# ProDocument_Board1612_2023-10-08.net
KiCad netlist of a schematic drawn in EasyEDA Pro
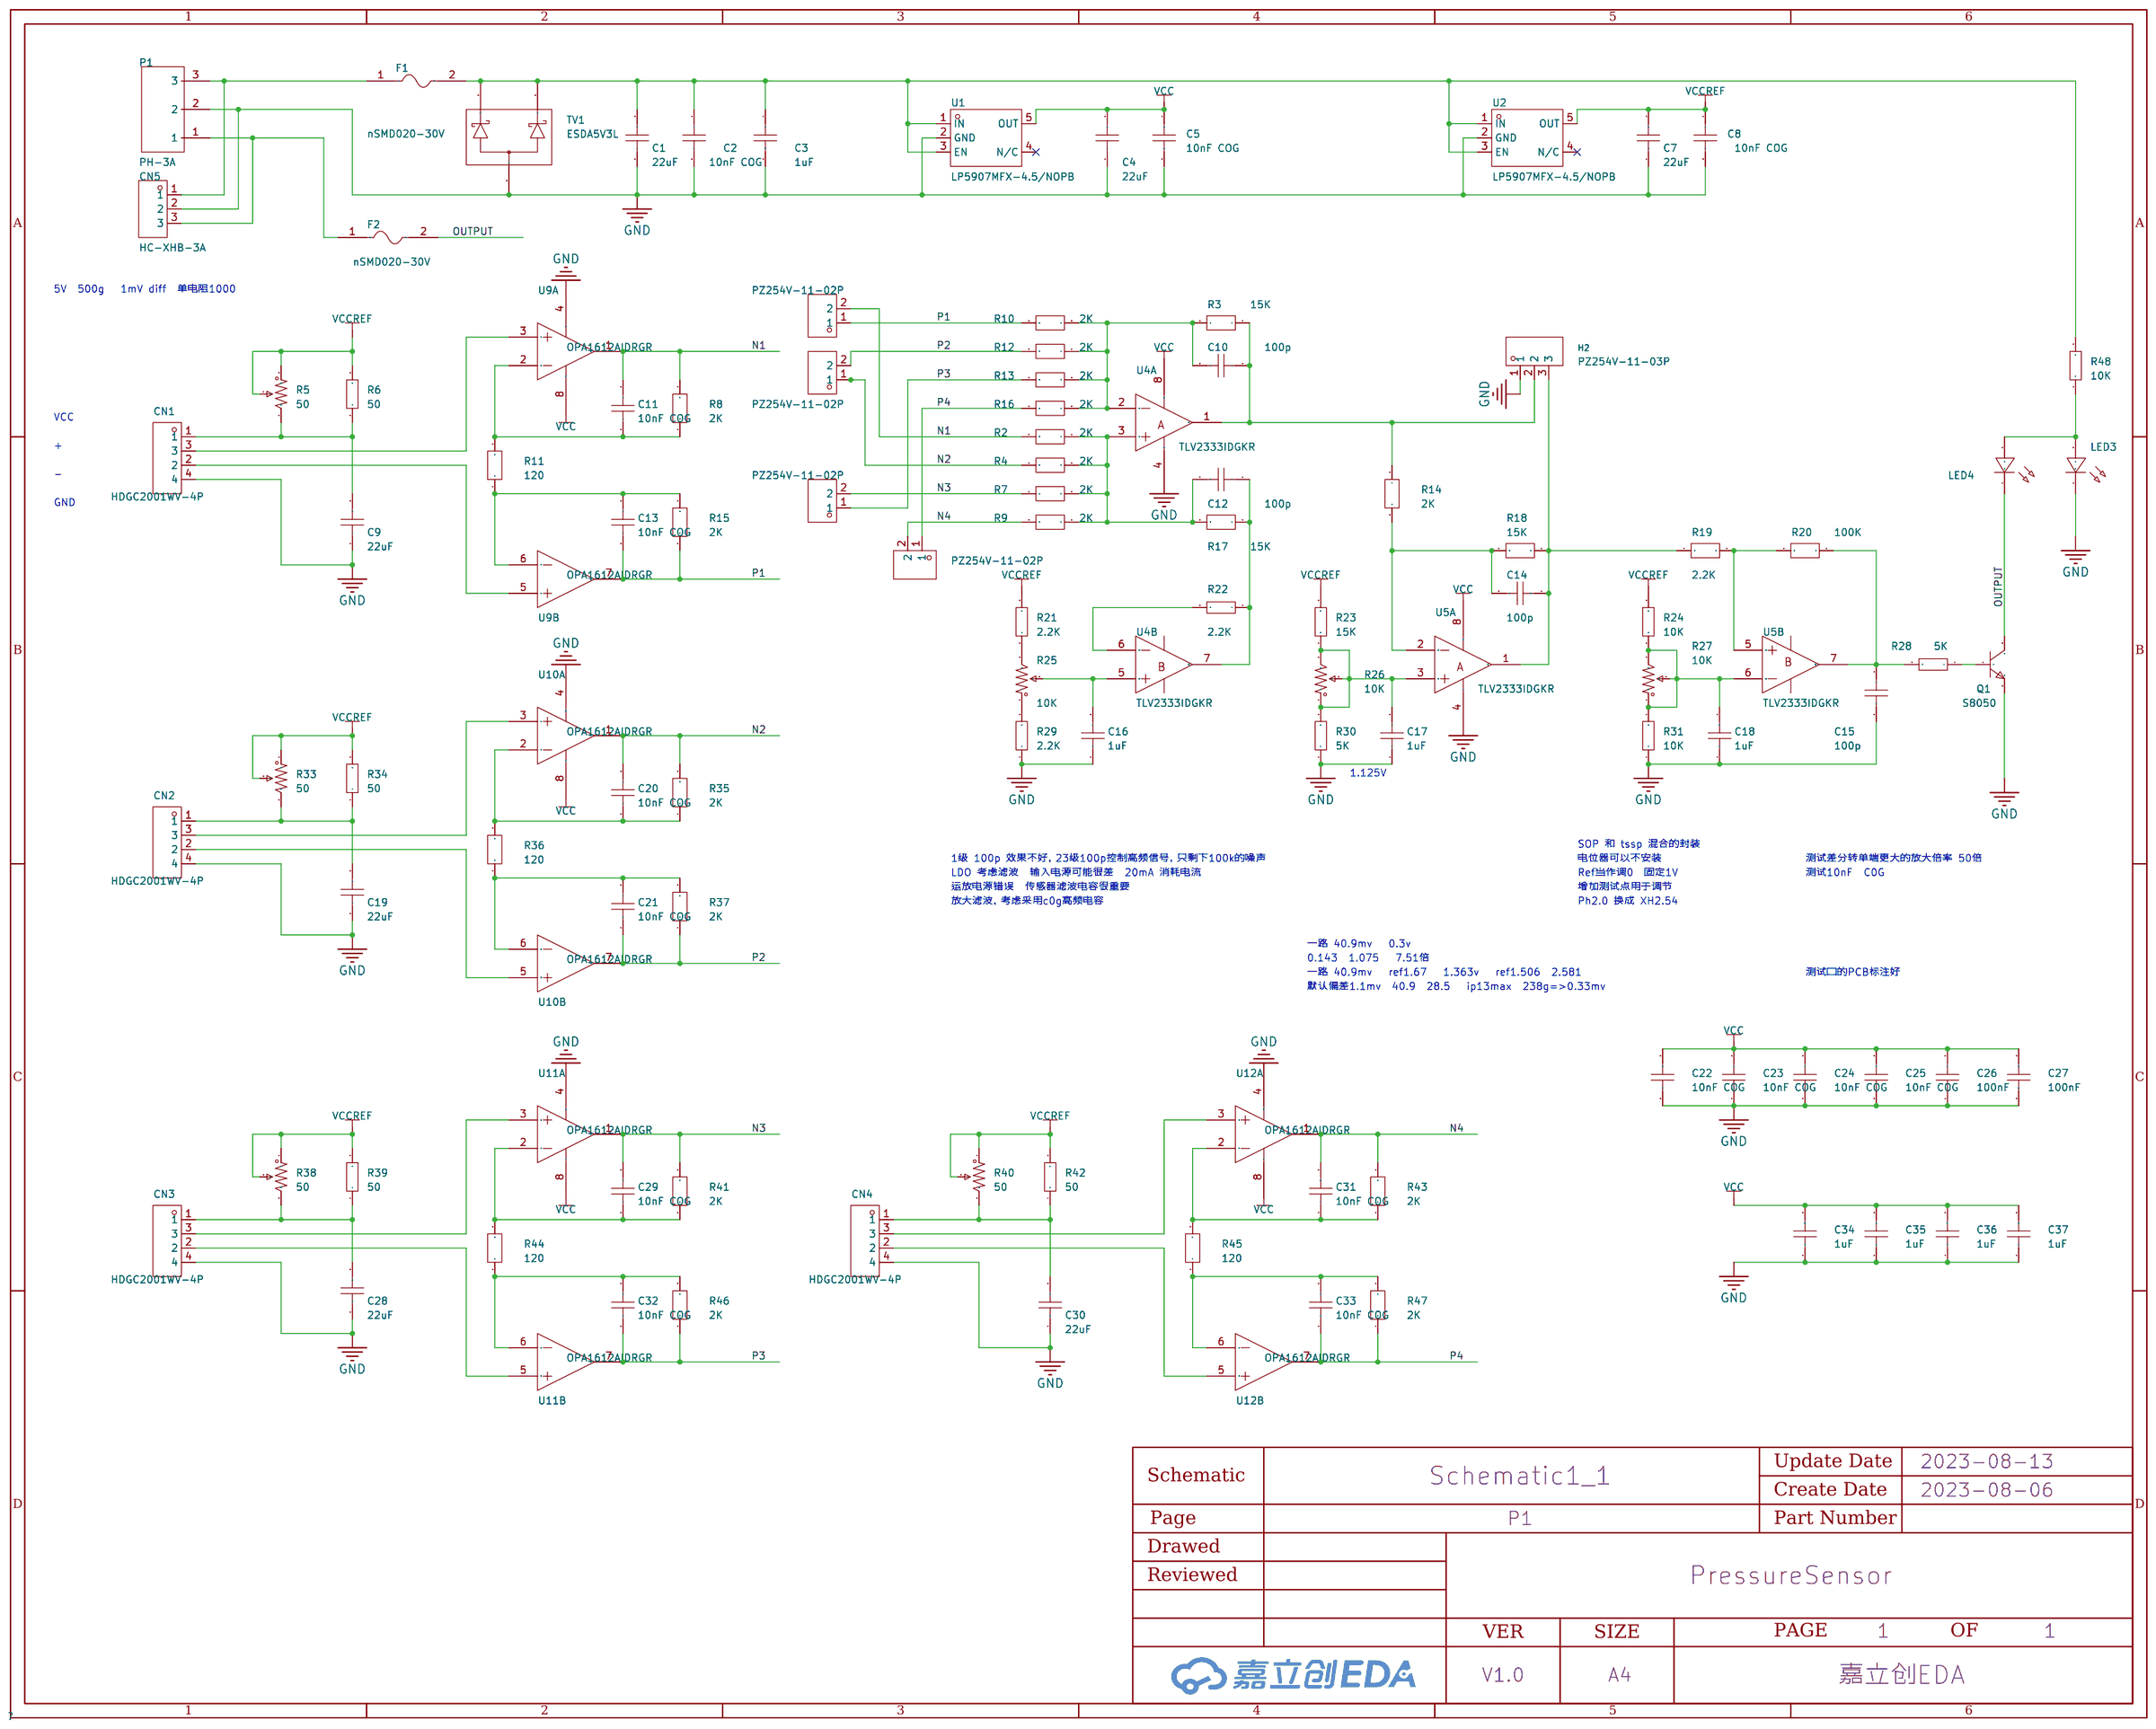
[diagram p0: schematic sheet]

(export (version "E")
  (design (tool "Eeschema 10.0.6"))
  (components
    (comp (ref "C1")
      (value "22uF")
      (footprint "easyedapro:R0402")
      (libsource (lib "easyedapro") (part "CapAcitance"))
    )
    (comp (ref "C2")
      (value "10nF COG")
      (footprint "easyedapro:R0402")
      (libsource (lib "easyedapro") (part "CapAcitance"))
    )
    (comp (ref "C3")
      (value "1uF")
      (footprint "easyedapro:R0402")
      (libsource (lib "easyedapro") (part "CapAcitance"))
    )
    (comp (ref "C4")
      (value "22uF")
      (footprint "easyedapro:R0402")
      (libsource (lib "easyedapro") (part "CapAcitance"))
    )
    (comp (ref "C5")
      (value "10nF COG")
      (footprint "easyedapro:R0402")
      (libsource (lib "easyedapro") (part "CapAcitance"))
    )
    (comp (ref "C7")
      (value "22uF")
      (footprint "easyedapro:R0402")
      (libsource (lib "easyedapro") (part "CapAcitance"))
    )
    (comp (ref "C8")
      (value "10nF COG")
      (footprint "easyedapro:R0402")
      (libsource (lib "easyedapro") (part "CapAcitance"))
    )
    (comp (ref "C9")
      (value "22uF")
      (footprint "easyedapro:R0402")
      (libsource (lib "easyedapro") (part "CapAcitance"))
    )
    (comp (ref "C10")
      (value "100p")
      (footprint "easyedapro:R0402")
      (libsource (lib "easyedapro") (part "CapAcitance"))
    )
    (comp (ref "C11")
      (value "10nF COG")
      (footprint "easyedapro:R0402")
      (libsource (lib "easyedapro") (part "CapAcitance"))
    )
    (comp (ref "C12")
      (value "100p")
      (footprint "easyedapro:R0402")
      (libsource (lib "easyedapro") (part "CapAcitance"))
    )
    (comp (ref "C13")
      (value "10nF COG")
      (footprint "easyedapro:R0402")
      (libsource (lib "easyedapro") (part "CapAcitance"))
    )
    (comp (ref "C14")
      (value "100p")
      (footprint "easyedapro:R0402")
      (libsource (lib "easyedapro") (part "CapAcitance"))
    )
    (comp (ref "C15")
      (value "100p")
      (footprint "easyedapro:R0402")
      (libsource (lib "easyedapro") (part "CapAcitance"))
    )
    (comp (ref "C16")
      (value "1uF")
      (footprint "easyedapro:R0402")
      (libsource (lib "easyedapro") (part "CapAcitance"))
    )
    (comp (ref "C17")
      (value "1uF")
      (footprint "easyedapro:R0402")
      (libsource (lib "easyedapro") (part "CapAcitance"))
    )
    (comp (ref "C18")
      (value "1uF")
      (footprint "easyedapro:R0402")
      (libsource (lib "easyedapro") (part "CapAcitance"))
    )
    (comp (ref "C19")
      (value "22uF")
      (footprint "easyedapro:R0402")
      (libsource (lib "easyedapro") (part "CapAcitance"))
    )
    (comp (ref "C20")
      (value "10nF COG")
      (footprint "easyedapro:R0402")
      (libsource (lib "easyedapro") (part "CapAcitance"))
    )
    (comp (ref "C21")
      (value "10nF COG")
      (footprint "easyedapro:R0402")
      (libsource (lib "easyedapro") (part "CapAcitance"))
    )
    (comp (ref "C22")
      (value "10nF COG")
      (footprint "easyedapro:R0402")
      (libsource (lib "easyedapro") (part "CapAcitance"))
    )
    (comp (ref "C23")
      (value "10nF COG")
      (footprint "easyedapro:R0402")
      (libsource (lib "easyedapro") (part "CapAcitance"))
    )
    (comp (ref "C24")
      (value "10nF COG")
      (footprint "easyedapro:R0402")
      (libsource (lib "easyedapro") (part "CapAcitance"))
    )
    (comp (ref "C25")
      (value "10nF COG")
      (footprint "easyedapro:R0402")
      (libsource (lib "easyedapro") (part "CapAcitance"))
    )
    (comp (ref "C26")
      (value "100nF")
      (footprint "easyedapro:R0402")
      (libsource (lib "easyedapro") (part "CapAcitance"))
    )
    (comp (ref "C27")
      (value "100nF")
      (footprint "easyedapro:R0402")
      (libsource (lib "easyedapro") (part "CapAcitance"))
    )
    (comp (ref "C28")
      (value "22uF")
      (footprint "easyedapro:R0402")
      (libsource (lib "easyedapro") (part "CapAcitance"))
    )
    (comp (ref "C29")
      (value "10nF COG")
      (footprint "easyedapro:R0402")
      (libsource (lib "easyedapro") (part "CapAcitance"))
    )
    (comp (ref "C30")
      (value "22uF")
      (footprint "easyedapro:R0402")
      (libsource (lib "easyedapro") (part "CapAcitance"))
    )
    (comp (ref "C31")
      (value "10nF COG")
      (footprint "easyedapro:R0402")
      (libsource (lib "easyedapro") (part "CapAcitance"))
    )
    (comp (ref "C32")
      (value "10nF COG")
      (footprint "easyedapro:R0402")
      (libsource (lib "easyedapro") (part "CapAcitance"))
    )
    (comp (ref "C33")
      (value "10nF COG")
      (footprint "easyedapro:R0402")
      (libsource (lib "easyedapro") (part "CapAcitance"))
    )
    (comp (ref "C34")
      (value "1uF")
      (footprint "easyedapro:R0402")
      (libsource (lib "easyedapro") (part "CapAcitance"))
    )
    (comp (ref "C35")
      (value "1uF")
      (footprint "easyedapro:R0402")
      (libsource (lib "easyedapro") (part "CapAcitance"))
    )
    (comp (ref "C36")
      (value "1uF")
      (footprint "easyedapro:R0402")
      (libsource (lib "easyedapro") (part "CapAcitance"))
    )
    (comp (ref "C37")
      (value "1uF")
      (footprint "easyedapro:R0402")
      (libsource (lib "easyedapro") (part "CapAcitance"))
    )
    (comp (ref "CN1")
      (value "HDGC2001WV-4P")
      (footprint "easyedapro:CONN-TH_4P-P2.00_HDGC_HDGC2001WV-4P")
      (fields (field (name "Manufacturer") "HDGC(华德共创)"))
      (libsource (lib "easyedapro") (part "HDGC2001WV-4P"))
    )
    (comp (ref "CN2")
      (value "HDGC2001WV-4P")
      (footprint "easyedapro:CONN-TH_4P-P2.00_HDGC_HDGC2001WV-4P")
      (fields (field (name "Manufacturer") "HDGC(华德共创)"))
      (libsource (lib "easyedapro") (part "HDGC2001WV-4P"))
    )
    (comp (ref "CN3")
      (value "HDGC2001WV-4P")
      (footprint "easyedapro:CONN-TH_4P-P2.00_HDGC_HDGC2001WV-4P")
      (fields (field (name "Manufacturer") "HDGC(华德共创)"))
      (libsource (lib "easyedapro") (part "HDGC2001WV-4P"))
    )
    (comp (ref "CN4")
      (value "HDGC2001WV-4P")
      (footprint "easyedapro:CONN-TH_4P-P2.00_HDGC_HDGC2001WV-4P")
      (fields (field (name "Manufacturer") "HDGC(华德共创)"))
      (libsource (lib "easyedapro") (part "HDGC2001WV-4P"))
    )
    (comp (ref "CN5")
      (value "HC-XHB-3A")
      (footprint "easyedapro:CONN-TH_3P-P2.50_HC-XHB-3A")
      (description "参考系列:-;间距:2.5mm;插针结构:1x3P;排数:1;每排PIN数:3;行距:-;公母:公型插针;安装方式:直插;额定电流:3A;工作温度范围:-25°C~+85°C;")
      (fields (field (name "Manufacturer") "HCTL(华灿天禄)"))
      (libsource (lib "easyedapro") (part "HC-XHB-3A"))
    )
    (comp (ref "F1")
      (value "nSMD020-30V")
      (footprint "easyedapro:F1206")
      (description "最大电压:30V;最大电流:100A;保持电流:200mA;跳闸电流:460mA;")
      (fields (field (name "Manufacturer") "台湾陆海"))
      (libsource (lib "easyedapro") (part "nSMD020-30V"))
    )
    (comp (ref "F2")
      (value "nSMD020-30V")
      (footprint "easyedapro:F1206")
      (description "最大电压:30V;最大电流:100A;保持电流:200mA;跳闸电流:460mA;")
      (fields (field (name "Manufacturer") "台湾陆海"))
      (libsource (lib "easyedapro") (part "nSMD020-30V"))
    )
    (comp (ref "H2")
      (value "PZ254V-11-03P")
      (footprint "easyedapro:HDR-TH_3P-P2.54-V-M")
      (fields (field (name "Manufacturer") "XFCN(兴飞)"))
      (libsource (lib "easyedapro") (part "PZ254V-11-03P_C2937625"))
    )
    (comp (ref "H5")
      (value "PZ254V-11-02P")
      (footprint "easyedapro:HDR-TH_2P-P2.54-V-M")
      (fields (field (name "Manufacturer") "XFCN(兴飞)"))
      (libsource (lib "easyedapro") (part "PZ254V-11-02P"))
    )
    (comp (ref "H6")
      (value "PZ254V-11-02P")
      (footprint "easyedapro:HDR-TH_2P-P2.54-V-M")
      (fields (field (name "Manufacturer") "XFCN(兴飞)"))
      (libsource (lib "easyedapro") (part "PZ254V-11-02P"))
    )
    (comp (ref "H7")
      (value "PZ254V-11-02P")
      (footprint "easyedapro:HDR-TH_2P-P2.54-V-M")
      (fields (field (name "Manufacturer") "XFCN(兴飞)"))
      (libsource (lib "easyedapro") (part "PZ254V-11-02P"))
    )
    (comp (ref "H8")
      (value "PZ254V-11-02P")
      (footprint "easyedapro:HDR-TH_2P-P2.54-V-M")
      (fields (field (name "Manufacturer") "XFCN(兴飞)"))
      (libsource (lib "easyedapro") (part "PZ254V-11-02P"))
    )
    (comp (ref "LED3")
      (value "~")
      (footprint "easyedapro:LED_0603")
      (libsource (lib "easyedapro") (part "LED_B"))
    )
    (comp (ref "LED4")
      (value "~")
      (footprint "easyedapro:LED_0603")
      (libsource (lib "easyedapro") (part "LED_B"))
    )
    (comp (ref "P1")
      (value "PH-3A")
      (footprint "easyedapro:CONN-TH_12P-P2.00-H-W4.8_PH-3A")
      (description "参考系列:PH;间距:2mm;插针结构:1x3P;排数:1;每排PIN数:3;行距:-;安装方式:-;触头材质:-;")
      (fields (field (name "Manufacturer") "BOOMELE(博穆精密)"))
      (libsource (lib "easyedapro") (part "PH-3A RHOS"))
    )
    (comp (ref "Q1")
      (value "S8050")
      (footprint "easyedapro:SOT-23-3_L2.9-W1.6-P1.90-LS2.8-BR")
      (description "晶体管类型:NPN;集射极击穿电压(Vceo):25V;集电极电流(Ic):500mA;功率(Pd):300mW;直流电流增益(hFE@Ic,Vce):120@50mA,1V;")
      (fields (field (name "Manufacturer") "CJ(江苏长电/长晶)"))
      (libsource (lib "easyedapro") (part "S8050_C105433"))
    )
    (comp (ref "R2")
      (value "2K")
      (footprint "easyedapro:R0402")
      (description "阻值:4.7Ω;精度:±0.1%;温度系数:±25ppm/°C;")
      (fields (field (name "Manufacturer Part") "ARG02BTC4R70") (field (name "Manufacturer") "Viking(光颉)"))
      (libsource (lib "easyedapro") (part "ARG02BTC4R70"))
    )
    (comp (ref "R3")
      (value "15K")
      (footprint "easyedapro:R0402")
      (description "阻值:4.7Ω;精度:±0.1%;温度系数:±25ppm/°C;")
      (fields (field (name "Manufacturer Part") "ARG02BTC4R70") (field (name "Manufacturer") "Viking(光颉)"))
      (libsource (lib "easyedapro") (part "ARG02BTC4R70"))
    )
    (comp (ref "R4")
      (value "2K")
      (footprint "easyedapro:R0402")
      (description "阻值:4.7Ω;精度:±0.1%;温度系数:±25ppm/°C;")
      (fields (field (name "Manufacturer Part") "ARG02BTC4R70") (field (name "Manufacturer") "Viking(光颉)"))
      (libsource (lib "easyedapro") (part "ARG02BTC4R70"))
    )
    (comp (ref "R5")
      (value "50")
      (footprint "easyedapro:RES-ADJ-TH_3P-L10.0-W10.0-P2.50-L")
      (description "阻值:10kΩ;精度:±10%;")
      (fields (field (name "Manufacturer Part") "3296W-1-103") (field (name "Manufacturer") "BOCHEN(博晨)"))
      (libsource (lib "easyedapro") (part "3296W-1-103"))
    )
    (comp (ref "R6") (value "50") (footprint "easyedapro:R0402") (libsource (lib "easyedapro") (part "电阻")))
    (comp (ref "R7")
      (value "2K")
      (footprint "easyedapro:R0402")
      (description "阻值:4.7Ω;精度:±0.1%;温度系数:±25ppm/°C;")
      (fields (field (name "Manufacturer Part") "ARG02BTC4R70") (field (name "Manufacturer") "Viking(光颉)"))
      (libsource (lib "easyedapro") (part "ARG02BTC4R70"))
    )
    (comp (ref "R8")
      (value "2K")
      (footprint "easyedapro:R0402")
      (description "阻值:4.7Ω;精度:±0.1%;温度系数:±25ppm/°C;")
      (fields (field (name "Manufacturer Part") "ARG02BTC4R70") (field (name "Manufacturer") "Viking(光颉)"))
      (libsource (lib "easyedapro") (part "ARG02BTC4R70"))
    )
    (comp (ref "R9")
      (value "2K")
      (footprint "easyedapro:R0402")
      (description "阻值:4.7Ω;精度:±0.1%;温度系数:±25ppm/°C;")
      (fields (field (name "Manufacturer Part") "ARG02BTC4R70") (field (name "Manufacturer") "Viking(光颉)"))
      (libsource (lib "easyedapro") (part "ARG02BTC4R70"))
    )
    (comp (ref "R10")
      (value "2K")
      (footprint "easyedapro:R0402")
      (description "阻值:4.7Ω;精度:±0.1%;温度系数:±25ppm/°C;")
      (fields (field (name "Manufacturer Part") "ARG02BTC4R70") (field (name "Manufacturer") "Viking(光颉)"))
      (libsource (lib "easyedapro") (part "ARG02BTC4R70"))
    )
    (comp (ref "R11")
      (value "120")
      (footprint "easyedapro:R0402")
      (description "阻值:4.7Ω;精度:±0.1%;温度系数:±25ppm/°C;")
      (fields (field (name "Manufacturer Part") "ARG02BTC4R70") (field (name "Manufacturer") "Viking(光颉)"))
      (libsource (lib "easyedapro") (part "ARG02BTC4R70"))
    )
    (comp (ref "R12")
      (value "2K")
      (footprint "easyedapro:R0402")
      (description "阻值:4.7Ω;精度:±0.1%;温度系数:±25ppm/°C;")
      (fields (field (name "Manufacturer Part") "ARG02BTC4R70") (field (name "Manufacturer") "Viking(光颉)"))
      (libsource (lib "easyedapro") (part "ARG02BTC4R70"))
    )
    (comp (ref "R13")
      (value "2K")
      (footprint "easyedapro:R0402")
      (description "阻值:4.7Ω;精度:±0.1%;温度系数:±25ppm/°C;")
      (fields (field (name "Manufacturer Part") "ARG02BTC4R70") (field (name "Manufacturer") "Viking(光颉)"))
      (libsource (lib "easyedapro") (part "ARG02BTC4R70"))
    )
    (comp (ref "R14")
      (value "2K")
      (footprint "easyedapro:R0402")
      (description "阻值:4.7Ω;精度:±0.1%;温度系数:±25ppm/°C;")
      (fields (field (name "Manufacturer Part") "ARG02BTC4R70") (field (name "Manufacturer") "Viking(光颉)"))
      (libsource (lib "easyedapro") (part "ARG02BTC4R70"))
    )
    (comp (ref "R15")
      (value "2K")
      (footprint "easyedapro:R0402")
      (description "阻值:4.7Ω;精度:±0.1%;温度系数:±25ppm/°C;")
      (fields (field (name "Manufacturer Part") "ARG02BTC4R70") (field (name "Manufacturer") "Viking(光颉)"))
      (libsource (lib "easyedapro") (part "ARG02BTC4R70"))
    )
    (comp (ref "R16")
      (value "2K")
      (footprint "easyedapro:R0402")
      (description "阻值:4.7Ω;精度:±0.1%;温度系数:±25ppm/°C;")
      (fields (field (name "Manufacturer Part") "ARG02BTC4R70") (field (name "Manufacturer") "Viking(光颉)"))
      (libsource (lib "easyedapro") (part "ARG02BTC4R70"))
    )
    (comp (ref "R17")
      (value "15K")
      (footprint "easyedapro:R0402")
      (description "阻值:4.7Ω;精度:±0.1%;温度系数:±25ppm/°C;")
      (fields (field (name "Manufacturer Part") "ARG02BTC4R70") (field (name "Manufacturer") "Viking(光颉)"))
      (libsource (lib "easyedapro") (part "ARG02BTC4R70"))
    )
    (comp (ref "R18")
      (value "15K")
      (footprint "easyedapro:R0402")
      (description "阻值:4.7Ω;精度:±0.1%;温度系数:±25ppm/°C;")
      (fields (field (name "Manufacturer Part") "ARG02BTC4R70") (field (name "Manufacturer") "Viking(光颉)"))
      (libsource (lib "easyedapro") (part "ARG02BTC4R70"))
    )
    (comp (ref "R19")
      (value "2.2K")
      (footprint "easyedapro:R0402")
      (description "阻值:4.7Ω;精度:±0.1%;温度系数:±25ppm/°C;")
      (fields (field (name "Manufacturer Part") "ARG02BTC4R70") (field (name "Manufacturer") "Viking(光颉)"))
      (libsource (lib "easyedapro") (part "ARG02BTC4R70"))
    )
    (comp (ref "R20")
      (value "100K")
      (footprint "easyedapro:R0402")
      (description "阻值:4.7Ω;精度:±0.1%;温度系数:±25ppm/°C;")
      (fields (field (name "Manufacturer Part") "ARG02BTC4R70") (field (name "Manufacturer") "Viking(光颉)"))
      (libsource (lib "easyedapro") (part "ARG02BTC4R70"))
    )
    (comp (ref "R21")
      (value "2.2K")
      (footprint "easyedapro:R0402")
      (libsource (lib "easyedapro") (part "电阻"))
    )
    (comp (ref "R22")
      (value "2.2K")
      (footprint "easyedapro:R0402")
      (libsource (lib "easyedapro") (part "电阻"))
    )
    (comp (ref "R23") (value "15K") (footprint "easyedapro:R0402") (libsource (lib "easyedapro") (part "电阻")))
    (comp (ref "R24") (value "10K") (footprint "easyedapro:R0402") (libsource (lib "easyedapro") (part "电阻")))
    (comp (ref "R25")
      (value "10K")
      (footprint "easyedapro:RES-ADJ-TH_3P-L10.0-W10.0-P2.50-L")
      (description "阻值:10kΩ;精度:±10%;")
      (fields (field (name "Manufacturer Part") "3296W-1-103") (field (name "Manufacturer") "BOCHEN(博晨)"))
      (libsource (lib "easyedapro") (part "3296W-1-103"))
    )
    (comp (ref "R26")
      (value "10K")
      (footprint "easyedapro:RES-ADJ-TH_3P-L10.0-W10.0-P2.50-L")
      (description "阻值:10kΩ;精度:±10%;")
      (fields (field (name "Manufacturer Part") "3296W-1-103") (field (name "Manufacturer") "BOCHEN(博晨)"))
      (libsource (lib "easyedapro") (part "3296W-1-103"))
    )
    (comp (ref "R27")
      (value "10K")
      (footprint "easyedapro:RES-ADJ-TH_3P-L10.0-W10.0-P2.50-L")
      (description "阻值:10kΩ;精度:±10%;")
      (fields (field (name "Manufacturer Part") "3296W-1-103") (field (name "Manufacturer") "BOCHEN(博晨)"))
      (libsource (lib "easyedapro") (part "3296W-1-103"))
    )
    (comp (ref "R28") (value "5K") (footprint "easyedapro:R0402") (libsource (lib "easyedapro") (part "电阻")))
    (comp (ref "R29")
      (value "2.2K")
      (footprint "easyedapro:R0402")
      (libsource (lib "easyedapro") (part "电阻"))
    )
    (comp (ref "R30") (value "5K") (footprint "easyedapro:R0402") (libsource (lib "easyedapro") (part "电阻")))
    (comp (ref "R31") (value "10K") (footprint "easyedapro:R0402") (libsource (lib "easyedapro") (part "电阻")))
    (comp (ref "R33")
      (value "50")
      (footprint "easyedapro:RES-ADJ-TH_3P-L10.0-W10.0-P2.50-L")
      (description "阻值:10kΩ;精度:±10%;")
      (fields (field (name "Manufacturer Part") "3296W-1-103") (field (name "Manufacturer") "BOCHEN(博晨)"))
      (libsource (lib "easyedapro") (part "3296W-1-103"))
    )
    (comp (ref "R34") (value "50") (footprint "easyedapro:R0402") (libsource (lib "easyedapro") (part "电阻")))
    (comp (ref "R35")
      (value "2K")
      (footprint "easyedapro:R0402")
      (description "阻值:4.7Ω;精度:±0.1%;温度系数:±25ppm/°C;")
      (fields (field (name "Manufacturer Part") "ARG02BTC4R70") (field (name "Manufacturer") "Viking(光颉)"))
      (libsource (lib "easyedapro") (part "ARG02BTC4R70"))
    )
    (comp (ref "R36")
      (value "120")
      (footprint "easyedapro:R0402")
      (description "阻值:4.7Ω;精度:±0.1%;温度系数:±25ppm/°C;")
      (fields (field (name "Manufacturer Part") "ARG02BTC4R70") (field (name "Manufacturer") "Viking(光颉)"))
      (libsource (lib "easyedapro") (part "ARG02BTC4R70"))
    )
    (comp (ref "R37")
      (value "2K")
      (footprint "easyedapro:R0402")
      (description "阻值:4.7Ω;精度:±0.1%;温度系数:±25ppm/°C;")
      (fields (field (name "Manufacturer Part") "ARG02BTC4R70") (field (name "Manufacturer") "Viking(光颉)"))
      (libsource (lib "easyedapro") (part "ARG02BTC4R70"))
    )
    (comp (ref "R38")
      (value "50")
      (footprint "easyedapro:RES-ADJ-TH_3P-L10.0-W10.0-P2.50-L")
      (description "阻值:10kΩ;精度:±10%;")
      (fields (field (name "Manufacturer Part") "3296W-1-103") (field (name "Manufacturer") "BOCHEN(博晨)"))
      (libsource (lib "easyedapro") (part "3296W-1-103"))
    )
    (comp (ref "R39") (value "50") (footprint "easyedapro:R0402") (libsource (lib "easyedapro") (part "电阻")))
    (comp (ref "R40")
      (value "50")
      (footprint "easyedapro:RES-ADJ-TH_3P-L10.0-W10.0-P2.50-L")
      (description "阻值:10kΩ;精度:±10%;")
      (fields (field (name "Manufacturer Part") "3296W-1-103") (field (name "Manufacturer") "BOCHEN(博晨)"))
      (libsource (lib "easyedapro") (part "3296W-1-103"))
    )
    (comp (ref "R41")
      (value "2K")
      (footprint "easyedapro:R0402")
      (description "阻值:4.7Ω;精度:±0.1%;温度系数:±25ppm/°C;")
      (fields (field (name "Manufacturer Part") "ARG02BTC4R70") (field (name "Manufacturer") "Viking(光颉)"))
      (libsource (lib "easyedapro") (part "ARG02BTC4R70"))
    )
    (comp (ref "R42") (value "50") (footprint "easyedapro:R0402") (libsource (lib "easyedapro") (part "电阻")))
    (comp (ref "R43")
      (value "2K")
      (footprint "easyedapro:R0402")
      (description "阻值:4.7Ω;精度:±0.1%;温度系数:±25ppm/°C;")
      (fields (field (name "Manufacturer Part") "ARG02BTC4R70") (field (name "Manufacturer") "Viking(光颉)"))
      (libsource (lib "easyedapro") (part "ARG02BTC4R70"))
    )
    (comp (ref "R44")
      (value "120")
      (footprint "easyedapro:R0402")
      (description "阻值:4.7Ω;精度:±0.1%;温度系数:±25ppm/°C;")
      (fields (field (name "Manufacturer Part") "ARG02BTC4R70") (field (name "Manufacturer") "Viking(光颉)"))
      (libsource (lib "easyedapro") (part "ARG02BTC4R70"))
    )
    (comp (ref "R45")
      (value "120")
      (footprint "easyedapro:R0402")
      (description "阻值:4.7Ω;精度:±0.1%;温度系数:±25ppm/°C;")
      (fields (field (name "Manufacturer Part") "ARG02BTC4R70") (field (name "Manufacturer") "Viking(光颉)"))
      (libsource (lib "easyedapro") (part "ARG02BTC4R70"))
    )
    (comp (ref "R46")
      (value "2K")
      (footprint "easyedapro:R0402")
      (description "阻值:4.7Ω;精度:±0.1%;温度系数:±25ppm/°C;")
      (fields (field (name "Manufacturer Part") "ARG02BTC4R70") (field (name "Manufacturer") "Viking(光颉)"))
      (libsource (lib "easyedapro") (part "ARG02BTC4R70"))
    )
    (comp (ref "R47")
      (value "2K")
      (footprint "easyedapro:R0402")
      (description "阻值:4.7Ω;精度:±0.1%;温度系数:±25ppm/°C;")
      (fields (field (name "Manufacturer Part") "ARG02BTC4R70") (field (name "Manufacturer") "Viking(光颉)"))
      (libsource (lib "easyedapro") (part "ARG02BTC4R70"))
    )
    (comp (ref "R48") (value "10K") (footprint "easyedapro:R0402") (libsource (lib "easyedapro") (part "电阻")))
    (comp (ref "TV1")
      (value "ESDA5V3L")
      (footprint "easyedapro:SOT-23-3_L2.9-W1.6-P1.90-LS2.8-BR")
      (fields (field (name "Manufacturer") "ST(意法半导体)"))
      (libsource (lib "easyedapro") (part "ESDA5V3L"))
    )
    (comp (ref "U1")
      (value "LP5907MFX-4.5/NOPB")
      (footprint "easyedapro:TSOT-23-5_L2.9-W1.6-P0.95-LS2.8-BR")
      (description "输出类型:-;")
      (fields (field (name "Manufacturer") "TI(德州仪器)"))
      (libsource (lib "easyedapro") (part "LP5907MFX-4.5/NOPB"))
    )
    (comp (ref "U2")
      (value "LP5907MFX-4.5/NOPB")
      (footprint "easyedapro:TSOT-23-5_L2.9-W1.6-P0.95-LS2.8-BR")
      (description "输出类型:-;")
      (fields (field (name "Manufacturer") "TI(德州仪器)"))
      (libsource (lib "easyedapro") (part "LP5907MFX-4.5/NOPB"))
    )
    (comp (ref "U4")
      (value "TLV2333IDGKR")
      (footprint "easyedapro:VSSOP-8_L3.0-W3.0-P0.65-LS5.0-BL")
      (description "放大器组数:-;")
      (fields (field (name "Manufacturer") "TI(德州仪器)"))
      (libsource (lib "easyedapro") (part "TLV2333IDGKR"))
    )
    (comp (ref "U5")
      (value "TLV2333IDGKR")
      (footprint "easyedapro:VSSOP-8_L3.0-W3.0-P0.65-LS5.0-BL")
      (description "放大器组数:-;")
      (fields (field (name "Manufacturer") "TI(德州仪器)"))
      (libsource (lib "easyedapro") (part "TLV2333IDGKR"))
    )
    (comp (ref "U9")
      (value "OPA1612AIDRGR")
      (footprint "easyedapro:SON-8_L3.0-W3.0-P0.50-TL-EP_OPA1612AIDRGR")
      (description "具有 1.1nV/√Hz 噪声和较低 THD 的高精度 SoundPlus 音频运算放大器 8-SON -40 to 85")
      (fields (field (name "Manufacturer") "TI(德州仪器)"))
      (libsource (lib "easyedapro") (part "OPA1612AIDRGR"))
    )
    (comp (ref "U10")
      (value "OPA1612AIDRGR")
      (footprint "easyedapro:SON-8_L3.0-W3.0-P0.50-TL-EP_OPA1612AIDRGR")
      (description "具有 1.1nV/√Hz 噪声和较低 THD 的高精度 SoundPlus 音频运算放大器 8-SON -40 to 85")
      (fields (field (name "Manufacturer") "TI(德州仪器)"))
      (libsource (lib "easyedapro") (part "OPA1612AIDRGR"))
    )
    (comp (ref "U11")
      (value "OPA1612AIDRGR")
      (footprint "easyedapro:SON-8_L3.0-W3.0-P0.50-TL-EP_OPA1612AIDRGR")
      (description "具有 1.1nV/√Hz 噪声和较低 THD 的高精度 SoundPlus 音频运算放大器 8-SON -40 to 85")
      (fields (field (name "Manufacturer") "TI(德州仪器)"))
      (libsource (lib "easyedapro") (part "OPA1612AIDRGR"))
    )
    (comp (ref "U12")
      (value "OPA1612AIDRGR")
      (footprint "easyedapro:SON-8_L3.0-W3.0-P0.50-TL-EP_OPA1612AIDRGR")
      (description "具有 1.1nV/√Hz 噪声和较低 THD 的高精度 SoundPlus 音频运算放大器 8-SON -40 to 85")
      (fields (field (name "Manufacturer") "TI(德州仪器)"))
      (libsource (lib "easyedapro") (part "OPA1612AIDRGR"))
    )
  )
  (nets
    (net (code "1") (name "/N1") (class "Default")
      (node (ref "C11") (pin "2") (pinfunction "2_2") (pintype "input"))
      (node (ref "H5") (pin "2") (pinfunction "2_2") (pintype "input"))
      (node (ref "R2") (pin "2") (pinfunction "2_2") (pintype "input"))
      (node (ref "R8") (pin "2") (pinfunction "2_2") (pintype "input"))
      (node (ref "U9") (pin "1") (pinfunction "OUTA_1") (pintype "output"))
    )
    (net (code "2") (name "/N2") (class "Default")
      (node (ref "C20") (pin "2") (pinfunction "2_2") (pintype "input"))
      (node (ref "H8") (pin "1") (pinfunction "1_1") (pintype "input"))
      (node (ref "R35") (pin "2") (pinfunction "2_2") (pintype "input"))
      (node (ref "R4") (pin "2") (pinfunction "2_2") (pintype "input"))
      (node (ref "U10") (pin "1") (pinfunction "OUTA_1") (pintype "output"))
    )
    (net (code "3") (name "/N3") (class "Default")
      (node (ref "C29") (pin "2") (pinfunction "2_2") (pintype "input"))
      (node (ref "H6") (pin "2") (pinfunction "2_2") (pintype "input"))
      (node (ref "R41") (pin "2") (pinfunction "2_2") (pintype "input"))
      (node (ref "R7") (pin "2") (pinfunction "2_2") (pintype "input"))
      (node (ref "U11") (pin "1") (pinfunction "OUTA_1") (pintype "output"))
    )
    (net (code "4") (name "/N4") (class "Default")
      (node (ref "C31") (pin "2") (pinfunction "2_2") (pintype "input"))
      (node (ref "H7") (pin "2") (pinfunction "2_2") (pintype "input"))
      (node (ref "R43") (pin "2") (pinfunction "2_2") (pintype "input"))
      (node (ref "R9") (pin "2") (pinfunction "2_2") (pintype "input"))
      (node (ref "U12") (pin "1") (pinfunction "OUTA_1") (pintype "output"))
    )
    (net (code "5") (name "/OUTPUT") (class "Default")
      (node (ref "F2") (pin "2") (pinfunction "2_2") (pintype "input"))
      (node (ref "LED4") (pin "1") (pinfunction "C_1") (pintype "input"))
      (node (ref "Q1") (pin "3") (pinfunction "3_3") (pintype "input"))
    )
    (net (code "6") (name "/P1") (class "Default")
      (node (ref "C13") (pin "1") (pinfunction "1_1") (pintype "input"))
      (node (ref "H5") (pin "1") (pinfunction "1_1") (pintype "input"))
      (node (ref "R10") (pin "2") (pinfunction "2_2") (pintype "input"))
      (node (ref "R15") (pin "1") (pinfunction "1_1") (pintype "input"))
      (node (ref "U9") (pin "7") (pinfunction "OUTB_7") (pintype "output"))
    )
    (net (code "7") (name "/P2") (class "Default")
      (node (ref "C21") (pin "1") (pinfunction "1_1") (pintype "input"))
      (node (ref "H8") (pin "2") (pinfunction "2_2") (pintype "input"))
      (node (ref "R12") (pin "2") (pinfunction "2_2") (pintype "input"))
      (node (ref "R37") (pin "1") (pinfunction "1_1") (pintype "input"))
      (node (ref "U10") (pin "7") (pinfunction "OUTB_7") (pintype "output"))
    )
    (net (code "8") (name "/P3") (class "Default")
      (node (ref "C32") (pin "1") (pinfunction "1_1") (pintype "input"))
      (node (ref "H6") (pin "1") (pinfunction "1_1") (pintype "input"))
      (node (ref "R13") (pin "2") (pinfunction "2_2") (pintype "input"))
      (node (ref "R46") (pin "1") (pinfunction "1_1") (pintype "input"))
      (node (ref "U11") (pin "7") (pinfunction "OUTB_7") (pintype "output"))
    )
    (net (code "9") (name "/P4") (class "Default")
      (node (ref "C33") (pin "1") (pinfunction "1_1") (pintype "input"))
      (node (ref "H7") (pin "1") (pinfunction "1_1") (pintype "input"))
      (node (ref "R16") (pin "2") (pinfunction "2_2") (pintype "input"))
      (node (ref "R47") (pin "1") (pinfunction "1_1") (pintype "input"))
      (node (ref "U12") (pin "7") (pinfunction "OUTB_7") (pintype "output"))
    )
    (net (code "10") (name "GND") (class "Default")
      (node (ref "C1") (pin "1") (pinfunction "1_1") (pintype "input"))
      (node (ref "C15") (pin "2") (pinfunction "2_2") (pintype "input"))
      (node (ref "C16") (pin "1") (pinfunction "1_1") (pintype "input"))
      (node (ref "C17") (pin "1") (pinfunction "1_1") (pintype "input"))
      (node (ref "C18") (pin "1") (pinfunction "1_1") (pintype "input"))
      (node (ref "C19") (pin "1") (pinfunction "1_1") (pintype "input"))
      (node (ref "C2") (pin "2") (pinfunction "2_2") (pintype "input"))
      (node (ref "C22") (pin "1") (pinfunction "1_1") (pintype "input"))
      (node (ref "C23") (pin "1") (pinfunction "1_1") (pintype "input"))
      (node (ref "C24") (pin "1") (pinfunction "1_1") (pintype "input"))
      (node (ref "C25") (pin "1") (pinfunction "1_1") (pintype "input"))
      (node (ref "C26") (pin "1") (pinfunction "1_1") (pintype "input"))
      (node (ref "C27") (pin "1") (pinfunction "1_1") (pintype "input"))
      (node (ref "C28") (pin "1") (pinfunction "1_1") (pintype "input"))
      (node (ref "C3") (pin "2") (pinfunction "2_2") (pintype "input"))
      (node (ref "C30") (pin "1") (pinfunction "1_1") (pintype "input"))
      (node (ref "C34") (pin "1") (pinfunction "1_1") (pintype "input"))
      (node (ref "C35") (pin "1") (pinfunction "1_1") (pintype "input"))
      (node (ref "C36") (pin "1") (pinfunction "1_1") (pintype "input"))
      (node (ref "C37") (pin "1") (pinfunction "1_1") (pintype "input"))
      (node (ref "C4") (pin "1") (pinfunction "1_1") (pintype "input"))
      (node (ref "C5") (pin "2") (pinfunction "2_2") (pintype "input"))
      (node (ref "C7") (pin "1") (pinfunction "1_1") (pintype "input"))
      (node (ref "C8") (pin "2") (pinfunction "2_2") (pintype "input"))
      (node (ref "C9") (pin "1") (pinfunction "1_1") (pintype "input"))
      (node (ref "CN1") (pin "4") (pinfunction "4_4") (pintype "input"))
      (node (ref "CN2") (pin "4") (pinfunction "4_4") (pintype "input"))
      (node (ref "CN3") (pin "4") (pinfunction "4_4") (pintype "input"))
      (node (ref "CN4") (pin "4") (pinfunction "4_4") (pintype "input"))
      (node (ref "CN5") (pin "2") (pinfunction "2_2") (pintype "input"))
      (node (ref "H2") (pin "1") (pinfunction "1_1") (pintype "input"))
      (node (ref "LED3") (pin "1") (pinfunction "C_1") (pintype "input"))
      (node (ref "P1") (pin "2") (pinfunction "2_2") (pintype "input"))
      (node (ref "Q1") (pin "2") (pinfunction "2_2") (pintype "input"))
      (node (ref "R29") (pin "1") (pinfunction "1_1") (pintype "input"))
      (node (ref "R30") (pin "1") (pinfunction "1_1") (pintype "input"))
      (node (ref "R31") (pin "1") (pinfunction "1_1") (pintype "input"))
      (node (ref "TV1") (pin "3") (pinfunction "3_3") (pintype "input"))
      (node (ref "U1") (pin "2") (pinfunction "GND_2") (pintype "input"))
      (node (ref "U10") (pin "4") (pinfunction "GND_4") (pintype "input"))
      (node (ref "U11") (pin "4") (pinfunction "GND_4") (pintype "input"))
      (node (ref "U12") (pin "4") (pinfunction "GND_4") (pintype "input"))
      (node (ref "U2") (pin "2") (pinfunction "GND_2") (pintype "input"))
      (node (ref "U4") (pin "4") (pinfunction "V-_4") (pintype "input"))
      (node (ref "U5") (pin "4") (pinfunction "V-_4") (pintype "input"))
      (node (ref "U9") (pin "4") (pinfunction "GND_4") (pintype "input"))
    )
    (net (code "11") (name "Net-(C9-Pad2)") (class "Default")
      (node (ref "C9") (pin "2") (pinfunction "2_2") (pintype "input"))
      (node (ref "CN1") (pin "1") (pinfunction "1_1") (pintype "input"))
      (node (ref "R5") (pin "3") (pinfunction "3_3") (pintype "input"))
      (node (ref "R6") (pin "1") (pinfunction "1_1") (pintype "input"))
    )
    (net (code "12") (name "Net-(C19-Pad2)") (class "Default")
      (node (ref "C19") (pin "2") (pinfunction "2_2") (pintype "input"))
      (node (ref "CN2") (pin "1") (pinfunction "1_1") (pintype "input"))
      (node (ref "R33") (pin "3") (pinfunction "3_3") (pintype "input"))
      (node (ref "R34") (pin "1") (pinfunction "1_1") (pintype "input"))
    )
    (net (code "13") (name "Net-(C28-Pad2)") (class "Default")
      (node (ref "C28") (pin "2") (pinfunction "2_2") (pintype "input"))
      (node (ref "CN3") (pin "1") (pinfunction "1_1") (pintype "input"))
      (node (ref "R38") (pin "3") (pinfunction "3_3") (pintype "input"))
      (node (ref "R39") (pin "1") (pinfunction "1_1") (pintype "input"))
    )
    (net (code "14") (name "Net-(C30-Pad2)") (class "Default")
      (node (ref "C30") (pin "2") (pinfunction "2_2") (pintype "input"))
      (node (ref "CN4") (pin "1") (pinfunction "1_1") (pintype "input"))
      (node (ref "R40") (pin "3") (pinfunction "3_3") (pintype "input"))
      (node (ref "R42") (pin "1") (pinfunction "1_1") (pintype "input"))
    )
    (net (code "15") (name "Net-(CN5-Pad1)") (class "Default")
      (node (ref "CN5") (pin "1") (pinfunction "1_1") (pintype "input"))
      (node (ref "F1") (pin "1") (pinfunction "1_1") (pintype "input"))
      (node (ref "P1") (pin "3") (pinfunction "3_3") (pintype "input"))
    )
    (net (code "16") (name "Net-(CN5-Pad3)") (class "Default")
      (node (ref "CN5") (pin "3") (pinfunction "3_3") (pintype "input"))
      (node (ref "F2") (pin "1") (pinfunction "1_1") (pintype "input"))
      (node (ref "P1") (pin "1") (pinfunction "1_1") (pintype "input"))
    )
    (net (code "17") (name "Net-(LED3-A)") (class "Default")
      (node (ref "LED3") (pin "2") (pinfunction "A_2") (pintype "input"))
      (node (ref "LED4") (pin "2") (pinfunction "A_2") (pintype "input"))
      (node (ref "R48") (pin "1") (pinfunction "1_1") (pintype "input"))
    )
    (net (code "18") (name "Net-(Q1-Pad1)") (class "Default")
      (node (ref "Q1") (pin "1") (pinfunction "1_1") (pintype "input"))
      (node (ref "R28") (pin "1") (pinfunction "1_1") (pintype "input"))
    )
    (net (code "19") (name "Net-(R21-Pad1)") (class "Default")
      (node (ref "R21") (pin "1") (pinfunction "1_1") (pintype "input"))
      (node (ref "R25") (pin "3") (pinfunction "3_3") (pintype "input"))
    )
    (net (code "20") (name "Net-(R25-Pad1)") (class "Default")
      (node (ref "R25") (pin "1") (pinfunction "1_1") (pintype "input"))
      (node (ref "R29") (pin "2") (pinfunction "2_2") (pintype "input"))
    )
    (net (code "21") (name "Net-(U1-EN)") (class "Default")
      (node (ref "C1") (pin "2") (pinfunction "2_2") (pintype "input"))
      (node (ref "C2") (pin "1") (pinfunction "1_1") (pintype "input"))
      (node (ref "C3") (pin "1") (pinfunction "1_1") (pintype "input"))
      (node (ref "F1") (pin "2") (pinfunction "2_2") (pintype "input"))
      (node (ref "R48") (pin "2") (pinfunction "2_2") (pintype "input"))
      (node (ref "TV1") (pin "1") (pinfunction "1_1") (pintype "input"))
      (node (ref "TV1") (pin "2") (pinfunction "2_2") (pintype "input"))
      (node (ref "U1") (pin "1") (pinfunction "IN_1") (pintype "input"))
      (node (ref "U1") (pin "3") (pinfunction "EN_3") (pintype "input"))
      (node (ref "U2") (pin "1") (pinfunction "IN_1") (pintype "input"))
      (node (ref "U2") (pin "3") (pinfunction "EN_3") (pintype "input"))
    )
    (net (code "22") (name "Net-(U4A-INA+)") (class "Default")
      (node (ref "C12") (pin "2") (pinfunction "2_2") (pintype "input"))
      (node (ref "R17") (pin "2") (pinfunction "2_2") (pintype "input"))
      (node (ref "R2") (pin "1") (pinfunction "1_1") (pintype "input"))
      (node (ref "R4") (pin "1") (pinfunction "1_1") (pintype "input"))
      (node (ref "R7") (pin "1") (pinfunction "1_1") (pintype "input"))
      (node (ref "R9") (pin "1") (pinfunction "1_1") (pintype "input"))
      (node (ref "U4") (pin "3") (pinfunction "INA+_3") (pintype "input"))
    )
    (net (code "23") (name "Net-(U4A-INA-)") (class "Default")
      (node (ref "C10") (pin "2") (pinfunction "2_2") (pintype "input"))
      (node (ref "R10") (pin "1") (pinfunction "1_1") (pintype "input"))
      (node (ref "R12") (pin "1") (pinfunction "1_1") (pintype "input"))
      (node (ref "R13") (pin "1") (pinfunction "1_1") (pintype "input"))
      (node (ref "R16") (pin "1") (pinfunction "1_1") (pintype "input"))
      (node (ref "R3") (pin "2") (pinfunction "2_2") (pintype "input"))
      (node (ref "U4") (pin "2") (pinfunction "INA-_2") (pintype "input"))
    )
    (net (code "24") (name "Net-(U4A-OUTA)") (class "Default")
      (node (ref "C10") (pin "1") (pinfunction "1_1") (pintype "input"))
      (node (ref "H2") (pin "2") (pinfunction "2_2") (pintype "input"))
      (node (ref "R14") (pin "1") (pinfunction "1_1") (pintype "input"))
      (node (ref "R3") (pin "1") (pinfunction "1_1") (pintype "input"))
      (node (ref "U4") (pin "1") (pinfunction "OUTA_1") (pintype "output"))
    )
    (net (code "25") (name "Net-(U4B-INB+)") (class "Default")
      (node (ref "C16") (pin "2") (pinfunction "2_2") (pintype "input"))
      (node (ref "R25") (pin "2") (pinfunction "2_2") (pintype "input"))
      (node (ref "U4") (pin "5") (pinfunction "INB+_5") (pintype "input"))
    )
    (net (code "26") (name "Net-(U4B-INB-)") (class "Default")
      (node (ref "R22") (pin "2") (pinfunction "2_2") (pintype "input"))
      (node (ref "U4") (pin "6") (pinfunction "INB-_6") (pintype "input"))
    )
    (net (code "27") (name "Net-(U4B-OUTB)") (class "Default")
      (node (ref "C12") (pin "1") (pinfunction "1_1") (pintype "input"))
      (node (ref "R17") (pin "1") (pinfunction "1_1") (pintype "input"))
      (node (ref "R22") (pin "1") (pinfunction "1_1") (pintype "input"))
      (node (ref "U4") (pin "7") (pinfunction "OUTB_7") (pintype "output"))
    )
    (net (code "28") (name "Net-(U5A-INA+)") (class "Default")
      (node (ref "C17") (pin "2") (pinfunction "2_2") (pintype "input"))
      (node (ref "R23") (pin "1") (pinfunction "1_1") (pintype "input"))
      (node (ref "R26") (pin "1") (pinfunction "1_1") (pintype "input"))
      (node (ref "R26") (pin "2") (pinfunction "2_2") (pintype "input"))
      (node (ref "R26") (pin "3") (pinfunction "3_3") (pintype "input"))
      (node (ref "R30") (pin "2") (pinfunction "2_2") (pintype "input"))
      (node (ref "U5") (pin "3") (pinfunction "INA+_3") (pintype "input"))
    )
    (net (code "29") (name "Net-(U5A-INA-)") (class "Default")
      (node (ref "C14") (pin "2") (pinfunction "2_2") (pintype "input"))
      (node (ref "R14") (pin "2") (pinfunction "2_2") (pintype "input"))
      (node (ref "R18") (pin "2") (pinfunction "2_2") (pintype "input"))
      (node (ref "U5") (pin "2") (pinfunction "INA-_2") (pintype "input"))
    )
    (net (code "30") (name "Net-(U5A-OUTA)") (class "Default")
      (node (ref "C14") (pin "1") (pinfunction "1_1") (pintype "input"))
      (node (ref "H2") (pin "3") (pinfunction "3_3") (pintype "input"))
      (node (ref "R18") (pin "1") (pinfunction "1_1") (pintype "input"))
      (node (ref "R19") (pin "1") (pinfunction "1_1") (pintype "input"))
      (node (ref "U5") (pin "1") (pinfunction "OUTA_1") (pintype "output"))
    )
    (net (code "31") (name "Net-(U5B-INB+)") (class "Default")
      (node (ref "R19") (pin "2") (pinfunction "2_2") (pintype "input"))
      (node (ref "R20") (pin "2") (pinfunction "2_2") (pintype "input"))
      (node (ref "U5") (pin "5") (pinfunction "INB+_5") (pintype "input"))
    )
    (net (code "32") (name "Net-(U5B-INB-)") (class "Default")
      (node (ref "C18") (pin "2") (pinfunction "2_2") (pintype "input"))
      (node (ref "R24") (pin "1") (pinfunction "1_1") (pintype "input"))
      (node (ref "R27") (pin "1") (pinfunction "1_1") (pintype "input"))
      (node (ref "R27") (pin "2") (pinfunction "2_2") (pintype "input"))
      (node (ref "R27") (pin "3") (pinfunction "3_3") (pintype "input"))
      (node (ref "R31") (pin "2") (pinfunction "2_2") (pintype "input"))
      (node (ref "U5") (pin "6") (pinfunction "INB-_6") (pintype "input"))
    )
    (net (code "33") (name "Net-(U5B-OUTB)") (class "Default")
      (node (ref "C15") (pin "1") (pinfunction "1_1") (pintype "input"))
      (node (ref "R20") (pin "1") (pinfunction "1_1") (pintype "input"))
      (node (ref "R28") (pin "2") (pinfunction "2_2") (pintype "input"))
      (node (ref "U5") (pin "7") (pinfunction "OUTB_7") (pintype "output"))
    )
    (net (code "34") (name "Net-(U9A-INA+)") (class "Default")
      (node (ref "CN1") (pin "3") (pinfunction "3_3") (pintype "input"))
      (node (ref "U9") (pin "3") (pinfunction "INA+_3") (pintype "input"))
    )
    (net (code "35") (name "Net-(U9A-INA-)") (class "Default")
      (node (ref "C11") (pin "1") (pinfunction "1_1") (pintype "input"))
      (node (ref "R11") (pin "2") (pinfunction "2_2") (pintype "input"))
      (node (ref "R8") (pin "1") (pinfunction "1_1") (pintype "input"))
      (node (ref "U9") (pin "2") (pinfunction "INA-_2") (pintype "input"))
    )
    (net (code "36") (name "Net-(U9B-INB+)") (class "Default")
      (node (ref "CN1") (pin "2") (pinfunction "2_2") (pintype "input"))
      (node (ref "U9") (pin "5") (pinfunction "INB+_5") (pintype "input"))
    )
    (net (code "37") (name "Net-(U9B-INB-)") (class "Default")
      (node (ref "C13") (pin "2") (pinfunction "2_2") (pintype "input"))
      (node (ref "R11") (pin "1") (pinfunction "1_1") (pintype "input"))
      (node (ref "R15") (pin "2") (pinfunction "2_2") (pintype "input"))
      (node (ref "U9") (pin "6") (pinfunction "INB-_6") (pintype "input"))
    )
    (net (code "38") (name "Net-(U10A-INA+)") (class "Default")
      (node (ref "CN2") (pin "3") (pinfunction "3_3") (pintype "input"))
      (node (ref "U10") (pin "3") (pinfunction "INA+_3") (pintype "input"))
    )
    (net (code "39") (name "Net-(U10A-INA-)") (class "Default")
      (node (ref "C20") (pin "1") (pinfunction "1_1") (pintype "input"))
      (node (ref "R35") (pin "1") (pinfunction "1_1") (pintype "input"))
      (node (ref "R36") (pin "2") (pinfunction "2_2") (pintype "input"))
      (node (ref "U10") (pin "2") (pinfunction "INA-_2") (pintype "input"))
    )
    (net (code "40") (name "Net-(U10B-INB+)") (class "Default")
      (node (ref "CN2") (pin "2") (pinfunction "2_2") (pintype "input"))
      (node (ref "U10") (pin "5") (pinfunction "INB+_5") (pintype "input"))
    )
    (net (code "41") (name "Net-(U10B-INB-)") (class "Default")
      (node (ref "C21") (pin "2") (pinfunction "2_2") (pintype "input"))
      (node (ref "R36") (pin "1") (pinfunction "1_1") (pintype "input"))
      (node (ref "R37") (pin "2") (pinfunction "2_2") (pintype "input"))
      (node (ref "U10") (pin "6") (pinfunction "INB-_6") (pintype "input"))
    )
    (net (code "42") (name "Net-(U11A-INA+)") (class "Default")
      (node (ref "CN3") (pin "3") (pinfunction "3_3") (pintype "input"))
      (node (ref "U11") (pin "3") (pinfunction "INA+_3") (pintype "input"))
    )
    (net (code "43") (name "Net-(U11A-INA-)") (class "Default")
      (node (ref "C29") (pin "1") (pinfunction "1_1") (pintype "input"))
      (node (ref "R41") (pin "1") (pinfunction "1_1") (pintype "input"))
      (node (ref "R44") (pin "2") (pinfunction "2_2") (pintype "input"))
      (node (ref "U11") (pin "2") (pinfunction "INA-_2") (pintype "input"))
    )
    (net (code "44") (name "Net-(U11B-INB+)") (class "Default")
      (node (ref "CN3") (pin "2") (pinfunction "2_2") (pintype "input"))
      (node (ref "U11") (pin "5") (pinfunction "INB+_5") (pintype "input"))
    )
    (net (code "45") (name "Net-(U11B-INB-)") (class "Default")
      (node (ref "C32") (pin "2") (pinfunction "2_2") (pintype "input"))
      (node (ref "R44") (pin "1") (pinfunction "1_1") (pintype "input"))
      (node (ref "R46") (pin "2") (pinfunction "2_2") (pintype "input"))
      (node (ref "U11") (pin "6") (pinfunction "INB-_6") (pintype "input"))
    )
    (net (code "46") (name "Net-(U12A-INA+)") (class "Default")
      (node (ref "CN4") (pin "3") (pinfunction "3_3") (pintype "input"))
      (node (ref "U12") (pin "3") (pinfunction "INA+_3") (pintype "input"))
    )
    (net (code "47") (name "Net-(U12A-INA-)") (class "Default")
      (node (ref "C31") (pin "1") (pinfunction "1_1") (pintype "input"))
      (node (ref "R43") (pin "1") (pinfunction "1_1") (pintype "input"))
      (node (ref "R45") (pin "2") (pinfunction "2_2") (pintype "input"))
      (node (ref "U12") (pin "2") (pinfunction "INA-_2") (pintype "input"))
    )
    (net (code "48") (name "Net-(U12B-INB+)") (class "Default")
      (node (ref "CN4") (pin "2") (pinfunction "2_2") (pintype "input"))
      (node (ref "U12") (pin "5") (pinfunction "INB+_5") (pintype "input"))
    )
    (net (code "49") (name "Net-(U12B-INB-)") (class "Default")
      (node (ref "C33") (pin "2") (pinfunction "2_2") (pintype "input"))
      (node (ref "R45") (pin "1") (pinfunction "1_1") (pintype "input"))
      (node (ref "R47") (pin "2") (pinfunction "2_2") (pintype "input"))
      (node (ref "U12") (pin "6") (pinfunction "INB-_6") (pintype "input"))
    )
    (net (code "50") (name "VCC") (class "Default")
      (node (ref "C22") (pin "2") (pinfunction "2_2") (pintype "input"))
      (node (ref "C23") (pin "2") (pinfunction "2_2") (pintype "input"))
      (node (ref "C24") (pin "2") (pinfunction "2_2") (pintype "input"))
      (node (ref "C25") (pin "2") (pinfunction "2_2") (pintype "input"))
      (node (ref "C26") (pin "2") (pinfunction "2_2") (pintype "input"))
      (node (ref "C27") (pin "2") (pinfunction "2_2") (pintype "input"))
      (node (ref "C34") (pin "2") (pinfunction "2_2") (pintype "input"))
      (node (ref "C35") (pin "2") (pinfunction "2_2") (pintype "input"))
      (node (ref "C36") (pin "2") (pinfunction "2_2") (pintype "input"))
      (node (ref "C37") (pin "2") (pinfunction "2_2") (pintype "input"))
      (node (ref "C4") (pin "2") (pinfunction "2_2") (pintype "input"))
      (node (ref "C5") (pin "1") (pinfunction "1_1") (pintype "input"))
      (node (ref "U1") (pin "5") (pinfunction "OUT_5") (pintype "input"))
      (node (ref "U10") (pin "8") (pinfunction "V+_8") (pintype "input"))
      (node (ref "U11") (pin "8") (pinfunction "V+_8") (pintype "input"))
      (node (ref "U12") (pin "8") (pinfunction "V+_8") (pintype "input"))
      (node (ref "U4") (pin "8") (pinfunction "V+_8") (pintype "input"))
      (node (ref "U5") (pin "8") (pinfunction "V+_8") (pintype "input"))
      (node (ref "U9") (pin "8") (pinfunction "V+_8") (pintype "input"))
    )
    (net (code "51") (name "VCCREF") (class "Default")
      (node (ref "C7") (pin "2") (pinfunction "2_2") (pintype "input"))
      (node (ref "C8") (pin "1") (pinfunction "1_1") (pintype "input"))
      (node (ref "R21") (pin "2") (pinfunction "2_2") (pintype "input"))
      (node (ref "R23") (pin "2") (pinfunction "2_2") (pintype "input"))
      (node (ref "R24") (pin "2") (pinfunction "2_2") (pintype "input"))
      (node (ref "R33") (pin "1") (pinfunction "1_1") (pintype "input"))
      (node (ref "R33") (pin "2") (pinfunction "2_2") (pintype "input"))
      (node (ref "R34") (pin "2") (pinfunction "2_2") (pintype "input"))
      (node (ref "R38") (pin "1") (pinfunction "1_1") (pintype "input"))
      (node (ref "R38") (pin "2") (pinfunction "2_2") (pintype "input"))
      (node (ref "R39") (pin "2") (pinfunction "2_2") (pintype "input"))
      (node (ref "R40") (pin "1") (pinfunction "1_1") (pintype "input"))
      (node (ref "R40") (pin "2") (pinfunction "2_2") (pintype "input"))
      (node (ref "R42") (pin "2") (pinfunction "2_2") (pintype "input"))
      (node (ref "R5") (pin "1") (pinfunction "1_1") (pintype "input"))
      (node (ref "R5") (pin "2") (pinfunction "2_2") (pintype "input"))
      (node (ref "R6") (pin "2") (pinfunction "2_2") (pintype "input"))
      (node (ref "U2") (pin "5") (pinfunction "OUT_5") (pintype "input"))
    )
    (net (code "52") (name "unconnected-(U1-N{slash}C-Pad4)") (class "Default")
      (node (ref "U1") (pin "4") (pinfunction "N/C_4") (pintype "input+no_connect"))
    )
    (net (code "53") (name "unconnected-(U2-N{slash}C-Pad4)") (class "Default")
      (node (ref "U2") (pin "4") (pinfunction "N/C_4") (pintype "input+no_connect"))
    )
  )
)
